# MainBoard_Light.net
KiCad netlist of a schematic drawn in Altium Designer
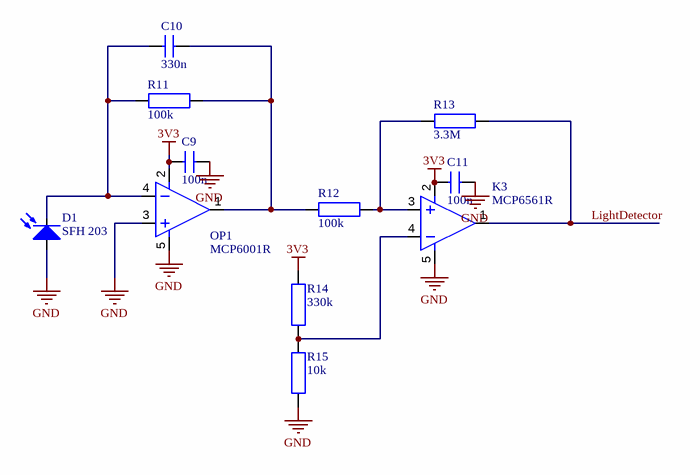
[diagram p0: MainBoard_Light.SchDoc]

(export (version "E")
  (design (tool "Eeschema 10.0.6"))
  (components
    (comp (ref "C9")
      (value "100n")
      (footprint "0805_C")
      (description "Normaler Kondensator")
      (libsource (lib "MainBoard") (part "C?"))
    )
    (comp (ref "C10")
      (value "330n")
      (footprint "0805_C")
      (description "Normaler Kondensator")
      (libsource (lib "MainBoard") (part "C?"))
    )
    (comp (ref "C11")
      (value "100n")
      (footprint "0805_C")
      (description "Normaler Kondensator")
      (libsource (lib "MainBoard") (part "C?"))
    )
    (comp (ref "D1")
      (value "SFH 203")
      (footprint "LED_THT_5mm_RM_2.54mm")
      (description "Photo_Diode_1A_2K")
      (libsource (lib "Sch_Lib") (part "Photo_Diode_1A_2K"))
    )
    (comp (ref "K3") (value "MCP6561R") (footprint "SOT23-5") (libsource (lib "") (part "OPAMP_1")))
    (comp (ref "OP1") (value "MCP6001R") (footprint "SOT23-5") (libsource (lib "MainBoard") (part "OPAMP")))
    (comp (ref "R11")
      (value "100k")
      (footprint "0805_R")
      (description "Normaler Widerstand")
      (libsource (lib "MainBoard") (part "R?"))
    )
    (comp (ref "R12")
      (value "100k")
      (footprint "0805_R")
      (description "Normaler Widerstand")
      (libsource (lib "MainBoard") (part "R?"))
    )
    (comp (ref "R13")
      (value "3.3M")
      (footprint "0805_R")
      (description "Normaler Widerstand")
      (libsource (lib "MainBoard") (part "R?"))
    )
    (comp (ref "R14")
      (value "330k")
      (footprint "0805_R")
      (description "Normaler Widerstand")
      (libsource (lib "MainBoard") (part "R?"))
    )
    (comp (ref "R15")
      (value "10k")
      (footprint "0805_R")
      (description "Normaler Widerstand")
      (libsource (lib "MainBoard") (part "R?"))
    )
  )
  (nets
    (net (code "1") (name "/LightDetector") (class "Default")
      (node (ref "K3") (pin "1") (pinfunction "1_1") (pintype "passive"))
      (node (ref "R13") (pin "1") (pintype "passive"))
    )
    (net (code "2") (name "3V3") (class "Default")
      (node (ref "C11") (pin "1") (pinfunction "1_1") (pintype "passive"))
      (node (ref "C9") (pin "1") (pinfunction "1_1") (pintype "passive"))
      (node (ref "K3") (pin "2") (pinfunction "2_2") (pintype "passive"))
      (node (ref "OP1") (pin "2") (pinfunction "2_2") (pintype "passive"))
      (node (ref "R14") (pin "1") (pintype "passive"))
    )
    (net (code "3") (name "GND") (class "Default")
      (node (ref "C11") (pin "2") (pinfunction "2_2") (pintype "passive"))
      (node (ref "C9") (pin "2") (pinfunction "2_2") (pintype "passive"))
      (node (ref "D1") (pin "1") (pinfunction "A_1") (pintype "passive"))
      (node (ref "K3") (pin "5") (pinfunction "5_5") (pintype "passive"))
      (node (ref "OP1") (pin "3") (pinfunction "3_3") (pintype "passive"))
      (node (ref "OP1") (pin "5") (pinfunction "5_5") (pintype "passive"))
      (node (ref "R15") (pin "2") (pintype "passive"))
    )
    (net (code "4") (name "Net-(C10-Pad2)") (class "Default")
      (node (ref "C10") (pin "2") (pinfunction "2_2") (pintype "passive"))
      (node (ref "OP1") (pin "1") (pinfunction "1_1") (pintype "passive"))
      (node (ref "R11") (pin "1") (pintype "passive"))
      (node (ref "R12") (pin "2") (pintype "passive"))
    )
    (net (code "5") (name "Net-(D1-K)") (class "Default")
      (node (ref "C10") (pin "1") (pinfunction "1_1") (pintype "passive"))
      (node (ref "D1") (pin "2") (pinfunction "K_2") (pintype "passive"))
      (node (ref "OP1") (pin "4") (pinfunction "4_4") (pintype "passive"))
      (node (ref "R11") (pin "2") (pintype "passive"))
    )
    (net (code "6") (name "Net-(K3-Pad3)") (class "Default")
      (node (ref "K3") (pin "3") (pinfunction "3_3") (pintype "passive"))
      (node (ref "R12") (pin "1") (pintype "passive"))
      (node (ref "R13") (pin "2") (pintype "passive"))
    )
    (net (code "7") (name "Net-(K3-Pad4)") (class "Default")
      (node (ref "K3") (pin "4") (pinfunction "4_4") (pintype "passive"))
      (node (ref "R14") (pin "2") (pintype "passive"))
      (node (ref "R15") (pin "1") (pintype "passive"))
    )
  )
)
